# Buffer_Out.net
KiCad netlist of a schematic drawn in Altium Designer
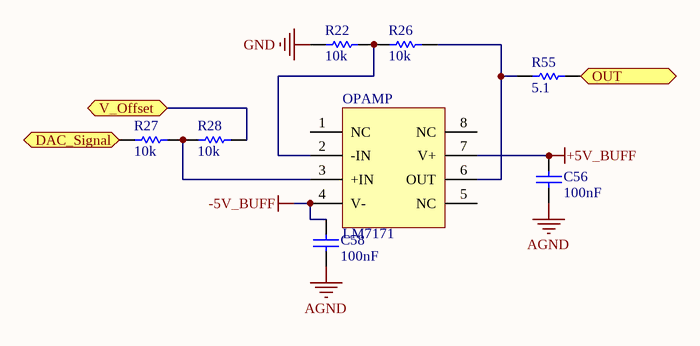
[diagram p0: Buffer_Out.SchDoc]

(export (version "E")
  (design (tool "Eeschema 10.0.6"))
  (components
    (comp (ref "C56")
      (value "100nF")
      (footprint "CAP_0603")
      (description "Capacitor")
      (fields (field (name "PUBLISHER") "Altium Limited"))
      (libsource (lib "Componentes_SOC") (part "Cap_0603"))
    )
    (comp (ref "C58")
      (value "100nF")
      (footprint "CAP_0603")
      (description "Capacitor")
      (fields (field (name "PUBLISHER") "Altium Limited"))
      (libsource (lib "Componentes_SOC") (part "Cap_0603"))
    )
    (comp (ref "OPAMP")
      (value "LM7171")
      (footprint "SOIC8_N")
      (description "IC OPAMP VFB 200MHZ 8SOIC")
      (libsource (lib "Componentes_SOC") (part "OPAMP"))
    )
    (comp (ref "R22")
      (value "10k")
      (footprint "RES_0603")
      (fields (field (name "PUBLISHER") "Altium Limited"))
      (libsource (lib "Componentes_SOC") (part "Res0603"))
    )
    (comp (ref "R26")
      (value "10k")
      (footprint "RES_0603")
      (fields (field (name "PUBLISHER") "Altium Limited"))
      (libsource (lib "Componentes_SOC") (part "Res0603"))
    )
    (comp (ref "R27")
      (value "10k")
      (footprint "RES_0603")
      (fields (field (name "PUBLISHER") "Altium Limited"))
      (libsource (lib "Componentes_SOC") (part "Res0603"))
    )
    (comp (ref "R28")
      (value "10k")
      (footprint "RES_0603")
      (fields (field (name "PUBLISHER") "Altium Limited"))
      (libsource (lib "Componentes_SOC") (part "Res0603"))
    )
    (comp (ref "R55")
      (value "5.1")
      (footprint "RES_0603")
      (fields (field (name "PUBLISHER") "Altium Limited"))
      (libsource (lib "Componentes_SOC") (part "Res0603"))
    )
  )
  (nets
    (net (code "1") (name "+5V_BUFF") (class "Default")
      (node (ref "C56") (pin "1") (pinfunction "1_1") (pintype "passive"))
      (node (ref "OPAMP") (pin "7") (pinfunction "V+_7") (pintype "passive"))
    )
    (net (code "2") (name "-5V_BUFF") (class "Default")
      (node (ref "C58") (pin "1") (pinfunction "1_1") (pintype "passive"))
      (node (ref "OPAMP") (pin "4") (pinfunction "V-_4") (pintype "passive"))
    )
    (net (code "3") (name "/DAC_Signal") (class "Default")
      (node (ref "R27") (pin "2") (pinfunction "2_2") (pintype "passive"))
    )
    (net (code "4") (name "/OUT") (class "Default")
      (node (ref "R55") (pin "1") (pinfunction "1_1") (pintype "passive"))
    )
    (net (code "5") (name "/V_Offset") (class "Default")
      (node (ref "R28") (pin "1") (pinfunction "1_1") (pintype "passive"))
    )
    (net (code "6") (name "AGND") (class "Default")
      (node (ref "C56") (pin "2") (pinfunction "2_2") (pintype "passive"))
      (node (ref "C58") (pin "2") (pinfunction "2_2") (pintype "passive"))
    )
    (net (code "7") (name "GND") (class "Default")
      (node (ref "R22") (pin "2") (pinfunction "2_2") (pintype "passive"))
    )
    (net (code "8") (name "Net-(OPAMP-+IN)") (class "Default")
      (node (ref "OPAMP") (pin "3") (pinfunction "+IN_3") (pintype "passive"))
      (node (ref "R27") (pin "1") (pinfunction "1_1") (pintype "passive"))
      (node (ref "R28") (pin "2") (pinfunction "2_2") (pintype "passive"))
    )
    (net (code "9") (name "Net-(OPAMP--IN)") (class "Default")
      (node (ref "OPAMP") (pin "2") (pinfunction "-IN_2") (pintype "passive"))
      (node (ref "R22") (pin "1") (pinfunction "1_1") (pintype "passive"))
      (node (ref "R26") (pin "2") (pinfunction "2_2") (pintype "passive"))
    )
    (net (code "10") (name "Net-(OPAMP-OUT)") (class "Default")
      (node (ref "OPAMP") (pin "6") (pinfunction "OUT_6") (pintype "passive"))
      (node (ref "R26") (pin "1") (pinfunction "1_1") (pintype "passive"))
      (node (ref "R55") (pin "2") (pinfunction "2_2") (pintype "passive"))
    )
    (net (code "11") (name "unconnected-(OPAMP-NC-Pad1)") (class "Default")
      (node (ref "OPAMP") (pin "1") (pinfunction "NC_1") (pintype "passive"))
    )
    (net (code "12") (name "unconnected-(OPAMP-NC-Pad5)") (class "Default")
      (node (ref "OPAMP") (pin "5") (pinfunction "NC_5") (pintype "passive"))
    )
    (net (code "13") (name "unconnected-(OPAMP-NC-Pad8)") (class "Default")
      (node (ref "OPAMP") (pin "8") (pinfunction "NC_8") (pintype "passive"))
    )
  )
)
